# DatacakeWing.net
KiCad netlist of a schematic drawn in EAGLE
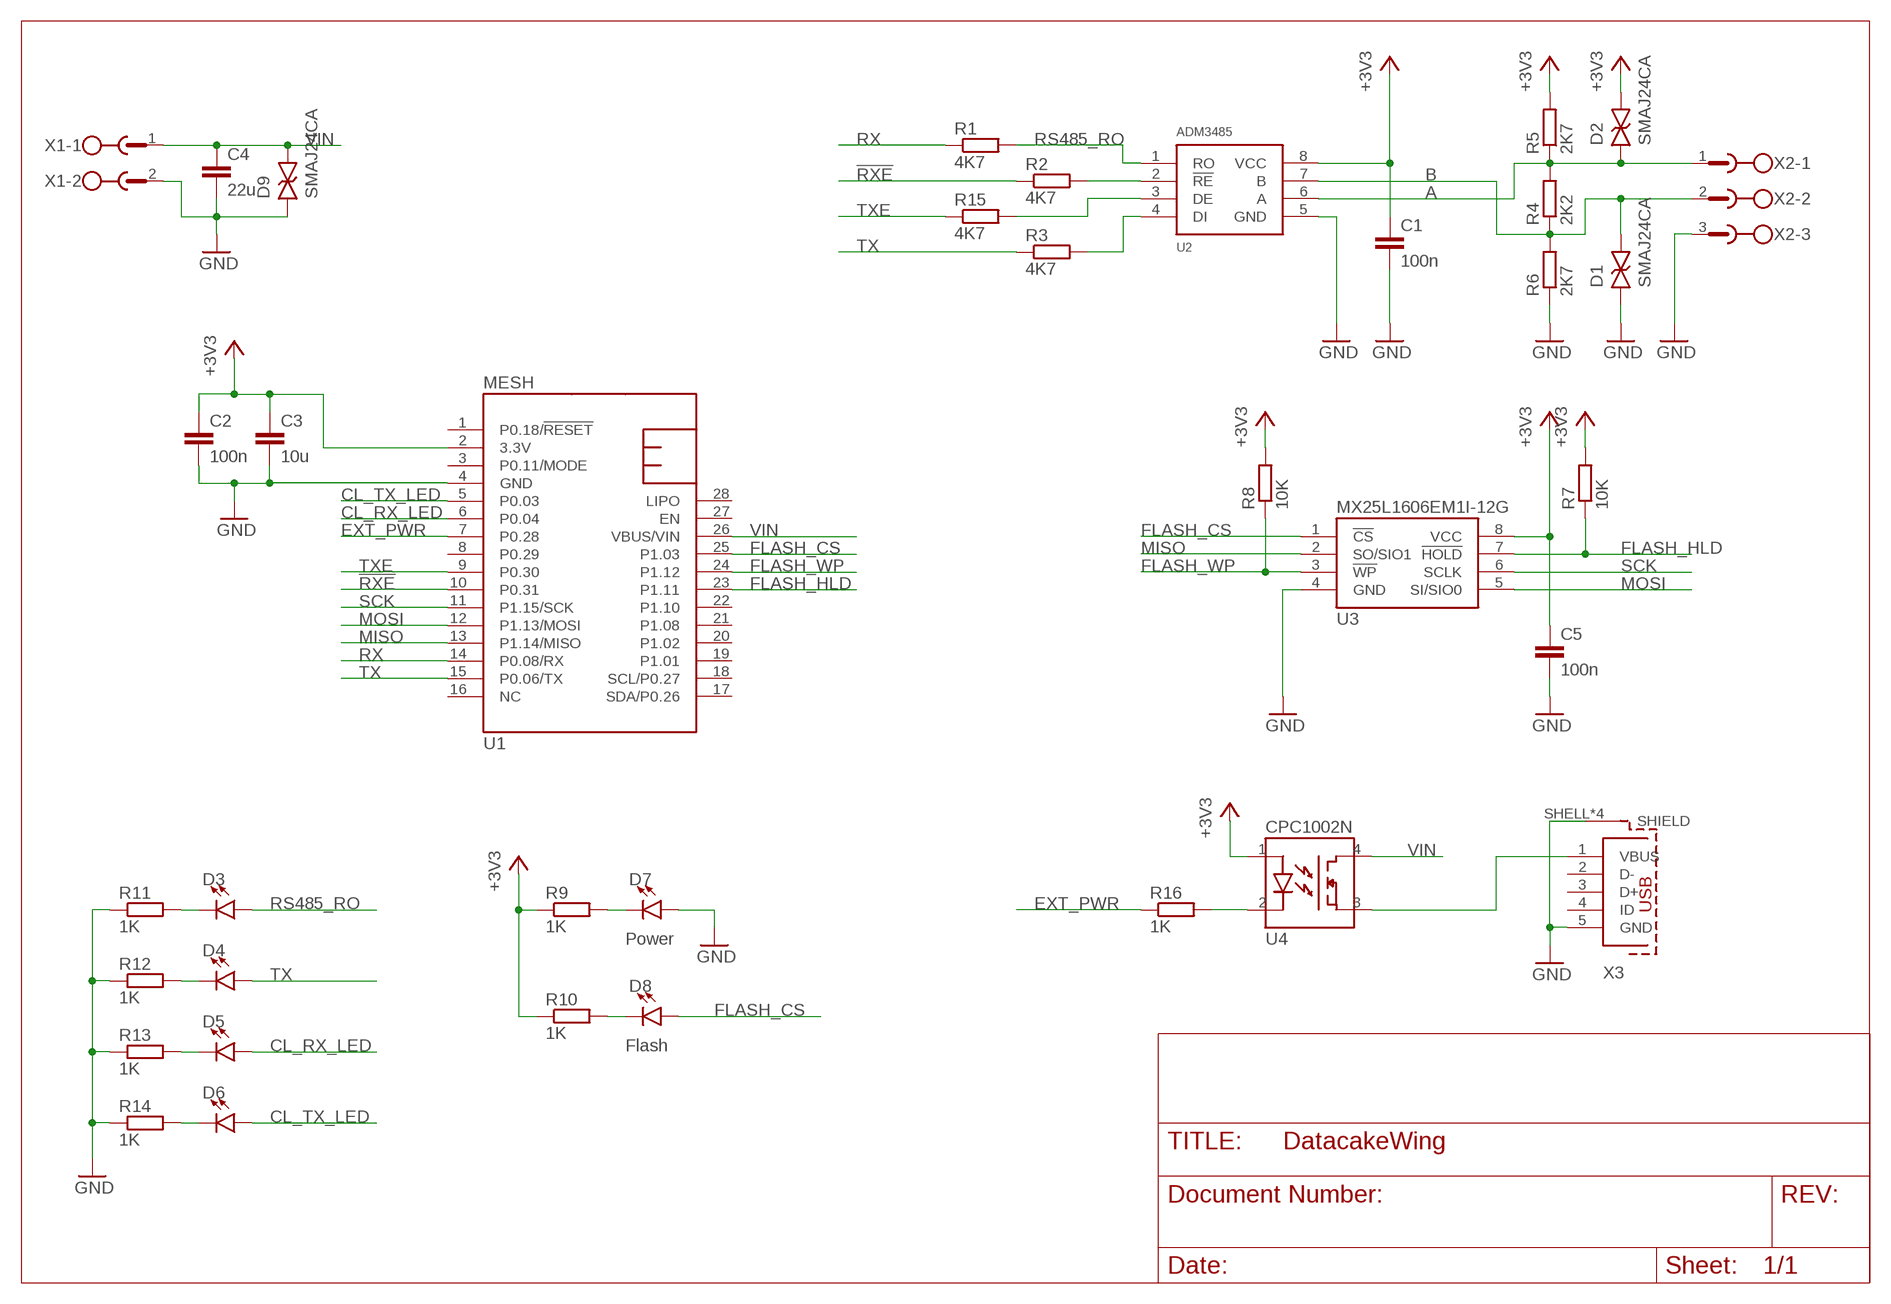
[diagram p0: schematic, sheet 1]

(export (version "E")
  (design (tool "Eeschema 10.0.6"))
  (components
    (comp (ref "C1")
      (value "100n")
      (footprint "eagle-import:C0603")
      (libsource (lib "eagle-import") (part "C-EUC0603"))
    )
    (comp (ref "C2")
      (value "100n")
      (footprint "eagle-import:C0603")
      (libsource (lib "eagle-import") (part "C-EUC0603"))
    )
    (comp (ref "C3")
      (value "10u")
      (footprint "eagle-import:C0603")
      (libsource (lib "eagle-import") (part "C-EUC0603"))
    )
    (comp (ref "C4")
      (value "22u")
      (footprint "eagle-import:C1210")
      (libsource (lib "eagle-import") (part "C-EUC1210"))
    )
    (comp (ref "C5")
      (value "100n")
      (footprint "eagle-import:C0603")
      (libsource (lib "eagle-import") (part "C-EUC0603"))
    )
    (comp (ref "D1")
      (value "SMAJ24CA")
      (footprint "eagle-import:DO-214AC")
      (libsource (lib "eagle-import") (part "SMAJ24CA"))
    )
    (comp (ref "D2")
      (value "SMAJ24CA")
      (footprint "eagle-import:DO-214AC")
      (libsource (lib "eagle-import") (part "SMAJ24CA"))
    )
    (comp (ref "D3")
      (value "LED0603")
      (footprint "eagle-import:LED-0603")
      (libsource (lib "eagle-import") (part "LED0603"))
    )
    (comp (ref "D4")
      (value "LED0603")
      (footprint "eagle-import:LED-0603")
      (libsource (lib "eagle-import") (part "LED0603"))
    )
    (comp (ref "D5")
      (value "LED0603")
      (footprint "eagle-import:LED-0603")
      (libsource (lib "eagle-import") (part "LED0603"))
    )
    (comp (ref "D6")
      (value "LED0603")
      (footprint "eagle-import:LED-0603")
      (libsource (lib "eagle-import") (part "LED0603"))
    )
    (comp (ref "D7")
      (value "LED0603")
      (footprint "eagle-import:LED-0603")
      (libsource (lib "eagle-import") (part "LED0603"))
    )
    (comp (ref "D8")
      (value "LED0603")
      (footprint "eagle-import:LED-0603")
      (libsource (lib "eagle-import") (part "LED0603"))
    )
    (comp (ref "D9")
      (value "SMAJ24CA")
      (footprint "eagle-import:DO-214AC")
      (libsource (lib "eagle-import") (part "SMAJ24CA"))
    )
    (comp (ref "R1")
      (value "4K7")
      (footprint "eagle-import:R0402")
      (libsource (lib "eagle-import") (part "R-EU_R0402"))
    )
    (comp (ref "R2")
      (value "4K7")
      (footprint "eagle-import:R0402")
      (libsource (lib "eagle-import") (part "R-EU_R0402"))
    )
    (comp (ref "R3")
      (value "4K7")
      (footprint "eagle-import:R0402")
      (libsource (lib "eagle-import") (part "R-EU_R0402"))
    )
    (comp (ref "R4")
      (value "2K2")
      (footprint "eagle-import:R0402")
      (libsource (lib "eagle-import") (part "R-EU_R0402"))
    )
    (comp (ref "R5")
      (value "2K7")
      (footprint "eagle-import:R0402")
      (libsource (lib "eagle-import") (part "R-EU_R0402"))
    )
    (comp (ref "R6")
      (value "2K7")
      (footprint "eagle-import:R0402")
      (libsource (lib "eagle-import") (part "R-EU_R0402"))
    )
    (comp (ref "R7")
      (value "10K")
      (footprint "eagle-import:R0402")
      (libsource (lib "eagle-import") (part "R-EU_R0402"))
    )
    (comp (ref "R8")
      (value "10K")
      (footprint "eagle-import:R0402")
      (libsource (lib "eagle-import") (part "R-EU_R0402"))
    )
    (comp (ref "R9")
      (value "1K")
      (footprint "eagle-import:R0402")
      (libsource (lib "eagle-import") (part "R-EU_R0402"))
    )
    (comp (ref "R10")
      (value "1K")
      (footprint "eagle-import:R0402")
      (libsource (lib "eagle-import") (part "R-EU_R0402"))
    )
    (comp (ref "R11")
      (value "1K")
      (footprint "eagle-import:R0402")
      (libsource (lib "eagle-import") (part "R-EU_R0402"))
    )
    (comp (ref "R12")
      (value "1K")
      (footprint "eagle-import:R0402")
      (libsource (lib "eagle-import") (part "R-EU_R0402"))
    )
    (comp (ref "R13")
      (value "1K")
      (footprint "eagle-import:R0402")
      (libsource (lib "eagle-import") (part "R-EU_R0402"))
    )
    (comp (ref "R14")
      (value "1K")
      (footprint "eagle-import:R0402")
      (libsource (lib "eagle-import") (part "R-EU_R0402"))
    )
    (comp (ref "R15")
      (value "4K7")
      (footprint "eagle-import:R0402")
      (libsource (lib "eagle-import") (part "R-EU_R0402"))
    )
    (comp (ref "R16")
      (value "1K")
      (footprint "eagle-import:R0402")
      (libsource (lib "eagle-import") (part "R-EU_R0402"))
    )
    (comp (ref "U1")
      (value "MESH")
      (footprint "eagle-import:FEATHERWING")
      (libsource (lib "eagle-import") (part "MESH"))
    )
    (comp (ref "U2")
      (value "ADM3485")
      (footprint "eagle-import:SO08-0.15")
      (libsource (lib "eagle-import") (part "ADM3485"))
    )
    (comp (ref "U3")
      (value "MX25L1606EM1I-12G")
      (footprint "eagle-import:SO08-0.15")
      (libsource (lib "eagle-import") (part "MX25L1606EM1I-12G"))
    )
    (comp (ref "U4")
      (value "CPC1002N")
      (footprint "eagle-import:CPC1002N")
      (libsource (lib "eagle-import") (part "CPC1002N"))
    )
    (comp (ref "X1")
      (value "MC1,5/2-G-3,5")
      (footprint "eagle-import:MC-2")
      (libsource (lib "eagle-import") (part "MC1,5/2-G-3,5"))
    )
    (comp (ref "X2")
      (value "MC1,5/3-G-3,5")
      (footprint "eagle-import:MC-3")
      (libsource (lib "eagle-import") (part "MC1,5/3-G-3,5"))
    )
    (comp (ref "X3")
      (value "629105136821")
      (footprint "eagle-import:629105136821")
      (libsource (lib "eagle-import") (part "629105136821"))
    )
  )
  (nets
    (net (code "1") (name "+3V3") (class "Default")
      (node (ref "C1") (pin "1") (pinfunction "1_1") (pintype "passive"))
      (node (ref "C2") (pin "1") (pinfunction "1_1") (pintype "passive"))
      (node (ref "C3") (pin "1") (pinfunction "1_1") (pintype "passive"))
      (node (ref "C5") (pin "1") (pinfunction "1_1") (pintype "passive"))
      (node (ref "D2") (pin "2") (pinfunction "P$2_2") (pintype "passive"))
      (node (ref "R10") (pin "1") (pinfunction "1_1") (pintype "passive"))
      (node (ref "R5") (pin "2") (pinfunction "2_2") (pintype "passive"))
      (node (ref "R7") (pin "2") (pinfunction "2_2") (pintype "passive"))
      (node (ref "R8") (pin "2") (pinfunction "2_2") (pintype "passive"))
      (node (ref "R9") (pin "1") (pinfunction "1_1") (pintype "passive"))
      (node (ref "U1") (pin "2") (pinfunction "3.3V_2") (pintype "power_in"))
      (node (ref "U2") (pin "8") (pinfunction "VCC_8") (pintype "bidirectional"))
      (node (ref "U3") (pin "8") (pinfunction "VCC_8") (pintype "bidirectional"))
      (node (ref "U4") (pin "1") (pinfunction "1_1") (pintype "passive"))
    )
    (net (code "2") (name "/A") (class "Default")
      (node (ref "D2") (pin "1") (pinfunction "P$1_1") (pintype "passive"))
      (node (ref "R4") (pin "2") (pinfunction "2_2") (pintype "passive"))
      (node (ref "R5") (pin "1") (pinfunction "1_1") (pintype "passive"))
      (node (ref "U2") (pin "6") (pinfunction "A_6") (pintype "bidirectional"))
      (node (ref "X2") (pin "1") (pinfunction "1_1") (pintype "passive"))
    )
    (net (code "3") (name "/B") (class "Default")
      (node (ref "D1") (pin "2") (pinfunction "P$2_2") (pintype "passive"))
      (node (ref "R4") (pin "1") (pinfunction "1_1") (pintype "passive"))
      (node (ref "R6") (pin "2") (pinfunction "2_2") (pintype "passive"))
      (node (ref "U2") (pin "7") (pinfunction "B_7") (pintype "bidirectional"))
      (node (ref "X2") (pin "2") (pinfunction "1_2") (pintype "passive"))
    )
    (net (code "4") (name "/CL_RX_LED") (class "Default")
      (node (ref "D5") (pin "A") (pinfunction "A_A") (pintype "passive"))
      (node (ref "U1") (pin "6") (pinfunction "P0.04_6") (pintype "bidirectional"))
    )
    (net (code "5") (name "/CL_TX_LED") (class "Default")
      (node (ref "D6") (pin "A") (pinfunction "A_A") (pintype "passive"))
      (node (ref "U1") (pin "5") (pinfunction "P0.03_5") (pintype "bidirectional"))
    )
    (net (code "6") (name "/EXT_PWR") (class "Default")
      (node (ref "R16") (pin "1") (pinfunction "1_1") (pintype "passive"))
      (node (ref "U1") (pin "7") (pinfunction "P0.28_7") (pintype "bidirectional"))
    )
    (net (code "7") (name "/FLASH_CS") (class "Default")
      (node (ref "D8") (pin "A") (pinfunction "A_A") (pintype "passive"))
      (node (ref "U1") (pin "25") (pinfunction "P1.03_25") (pintype "bidirectional"))
      (node (ref "U3") (pin "1") (pinfunction "~{CS}_1") (pintype "bidirectional"))
    )
    (net (code "8") (name "/FLASH_HLD") (class "Default")
      (node (ref "R7") (pin "1") (pinfunction "1_1") (pintype "passive"))
      (node (ref "U1") (pin "23") (pinfunction "P1.11_23") (pintype "bidirectional"))
      (node (ref "U3") (pin "7") (pinfunction "~{HOLD}_7") (pintype "bidirectional"))
    )
    (net (code "9") (name "/FLASH_WP") (class "Default")
      (node (ref "R8") (pin "1") (pinfunction "1_1") (pintype "passive"))
      (node (ref "U1") (pin "24") (pinfunction "P1.12_24") (pintype "bidirectional"))
      (node (ref "U3") (pin "3") (pinfunction "~{WP}_3") (pintype "bidirectional"))
    )
    (net (code "10") (name "/LIPO") (class "Default")
      (node (ref "U1") (pin "28") (pinfunction "LIPO_28") (pintype "power_in"))
    )
    (net (code "11") (name "/MISO") (class "Default")
      (node (ref "U1") (pin "13") (pinfunction "P1.14/MISO_13") (pintype "bidirectional"))
      (node (ref "U3") (pin "2") (pinfunction "SO/SIO1_2") (pintype "bidirectional"))
    )
    (net (code "12") (name "/MOSI") (class "Default")
      (node (ref "U1") (pin "12") (pinfunction "P1.13/MOSI_12") (pintype "bidirectional"))
      (node (ref "U3") (pin "5") (pinfunction "SI/SIO0_5") (pintype "bidirectional"))
    )
    (net (code "13") (name "/RS485_RO") (class "Default")
      (node (ref "D3") (pin "A") (pinfunction "A_A") (pintype "passive"))
      (node (ref "R1") (pin "2") (pinfunction "2_2") (pintype "passive"))
      (node (ref "U2") (pin "1") (pinfunction "RO_1") (pintype "bidirectional"))
    )
    (net (code "14") (name "/RX") (class "Default")
      (node (ref "R1") (pin "1") (pinfunction "1_1") (pintype "passive"))
      (node (ref "U1") (pin "14") (pinfunction "P0.08/RX_14") (pintype "bidirectional"))
    )
    (net (code "15") (name "/SCK") (class "Default")
      (node (ref "U1") (pin "11") (pinfunction "P1.15/SCK_11") (pintype "bidirectional"))
      (node (ref "U3") (pin "6") (pinfunction "SCLK_6") (pintype "bidirectional"))
    )
    (net (code "16") (name "/TX") (class "Default")
      (node (ref "D4") (pin "A") (pinfunction "A_A") (pintype "passive"))
      (node (ref "R3") (pin "1") (pinfunction "1_1") (pintype "passive"))
      (node (ref "U1") (pin "15") (pinfunction "P0.06/TX_15") (pintype "bidirectional"))
    )
    (net (code "17") (name "/TXE") (class "Default")
      (node (ref "R15") (pin "1") (pinfunction "1_1") (pintype "passive"))
      (node (ref "U1") (pin "9") (pinfunction "P0.30_9") (pintype "bidirectional"))
    )
    (net (code "18") (name "/VIN") (class "Default")
      (node (ref "C4") (pin "1") (pinfunction "1_1") (pintype "passive"))
      (node (ref "D9") (pin "2") (pinfunction "P$2_2") (pintype "passive"))
      (node (ref "U1") (pin "26") (pinfunction "VBUS/VIN_26") (pintype "power_in"))
      (node (ref "U4") (pin "4") (pinfunction "4_4") (pintype "passive"))
      (node (ref "X1") (pin "1") (pinfunction "1_1") (pintype "passive"))
    )
    (net (code "19") (name "/~{RXE}") (class "Default")
      (node (ref "R2") (pin "1") (pinfunction "1_1") (pintype "passive"))
      (node (ref "U1") (pin "10") (pinfunction "P0.31_10") (pintype "bidirectional"))
    )
    (net (code "20") (name "GND") (class "Default")
      (node (ref "C1") (pin "2") (pinfunction "2_2") (pintype "passive"))
      (node (ref "C2") (pin "2") (pinfunction "2_2") (pintype "passive"))
      (node (ref "C3") (pin "2") (pinfunction "2_2") (pintype "passive"))
      (node (ref "C4") (pin "2") (pinfunction "2_2") (pintype "passive"))
      (node (ref "C5") (pin "2") (pinfunction "2_2") (pintype "passive"))
      (node (ref "D1") (pin "1") (pinfunction "P$1_1") (pintype "passive"))
      (node (ref "D7") (pin "A") (pinfunction "A_A") (pintype "passive"))
      (node (ref "D9") (pin "1") (pinfunction "P$1_1") (pintype "passive"))
      (node (ref "R11") (pin "1") (pinfunction "1_1") (pintype "passive"))
      (node (ref "R12") (pin "1") (pinfunction "1_1") (pintype "passive"))
      (node (ref "R13") (pin "1") (pinfunction "1_1") (pintype "passive"))
      (node (ref "R14") (pin "1") (pinfunction "1_1") (pintype "passive"))
      (node (ref "R6") (pin "1") (pinfunction "1_1") (pintype "passive"))
      (node (ref "U1") (pin "4") (pinfunction "GND_4") (pintype "power_in"))
      (node (ref "U2") (pin "5") (pinfunction "GND_5") (pintype "bidirectional"))
      (node (ref "U3") (pin "4") (pinfunction "GND_4") (pintype "bidirectional"))
      (node (ref "X1") (pin "2") (pinfunction "1_2") (pintype "passive"))
      (node (ref "X2") (pin "3") (pinfunction "1_3") (pintype "passive"))
      (node (ref "X3") (pin "5") (pinfunction "GND_5") (pintype "passive"))
      (node (ref "X3") (pin "SHELL") (pinfunction "SHIELD_SHELL") (pintype "passive"))
      (node (ref "X3") (pin "SHELL1") (pinfunction "SHIELD_SHELL1") (pintype "passive"))
      (node (ref "X3") (pin "SHELL2") (pinfunction "SHIELD_SHELL2") (pintype "passive"))
      (node (ref "X3") (pin "SHELL3") (pinfunction "SHIELD_SHELL3") (pintype "passive"))
    )
    (net (code "21") (name "Net-(D3-PadC)") (class "Default")
      (node (ref "D3") (pin "C") (pinfunction "C_C") (pintype "passive"))
      (node (ref "R11") (pin "2") (pinfunction "2_2") (pintype "passive"))
    )
    (net (code "22") (name "Net-(D4-PadC)") (class "Default")
      (node (ref "D4") (pin "C") (pinfunction "C_C") (pintype "passive"))
      (node (ref "R12") (pin "2") (pinfunction "2_2") (pintype "passive"))
    )
    (net (code "23") (name "Net-(D5-PadC)") (class "Default")
      (node (ref "D5") (pin "C") (pinfunction "C_C") (pintype "passive"))
      (node (ref "R13") (pin "2") (pinfunction "2_2") (pintype "passive"))
    )
    (net (code "24") (name "Net-(D6-PadC)") (class "Default")
      (node (ref "D6") (pin "C") (pinfunction "C_C") (pintype "passive"))
      (node (ref "R14") (pin "2") (pinfunction "2_2") (pintype "passive"))
    )
    (net (code "25") (name "Net-(D7-PadC)") (class "Default")
      (node (ref "D7") (pin "C") (pinfunction "C_C") (pintype "passive"))
      (node (ref "R9") (pin "2") (pinfunction "2_2") (pintype "passive"))
    )
    (net (code "26") (name "Net-(D8-PadC)") (class "Default")
      (node (ref "D8") (pin "C") (pinfunction "C_C") (pintype "passive"))
      (node (ref "R10") (pin "2") (pinfunction "2_2") (pintype "passive"))
    )
    (net (code "27") (name "Net-(R16-Pad2)") (class "Default")
      (node (ref "R16") (pin "2") (pinfunction "2_2") (pintype "passive"))
      (node (ref "U4") (pin "2") (pinfunction "2_2") (pintype "passive"))
    )
    (net (code "28") (name "Net-(U2-DE)") (class "Default")
      (node (ref "R15") (pin "2") (pinfunction "2_2") (pintype "passive"))
      (node (ref "U2") (pin "3") (pinfunction "DE_3") (pintype "bidirectional"))
    )
    (net (code "29") (name "Net-(U2-DI)") (class "Default")
      (node (ref "R3") (pin "2") (pinfunction "2_2") (pintype "passive"))
      (node (ref "U2") (pin "4") (pinfunction "DI_4") (pintype "bidirectional"))
    )
    (net (code "30") (name "Net-(U2-~{RE})") (class "Default")
      (node (ref "R2") (pin "2") (pinfunction "2_2") (pintype "passive"))
      (node (ref "U2") (pin "2") (pinfunction "~{RE}_2") (pintype "bidirectional"))
    )
    (net (code "31") (name "Net-(X3-VBUS)") (class "Default")
      (node (ref "U4") (pin "3") (pinfunction "3_3") (pintype "passive"))
      (node (ref "X3") (pin "1") (pinfunction "VBUS_1") (pintype "passive"))
    )
    (net (code "32") (name "unconnected-(U1-EN-Pad27)") (class "Default")
      (node (ref "U1") (pin "27") (pinfunction "EN_27") (pintype "passive"))
    )
    (net (code "33") (name "unconnected-(U1-NC-Pad16)") (class "Default")
      (node (ref "U1") (pin "16") (pinfunction "NC_16") (pintype "passive"))
    )
    (net (code "34") (name "unconnected-(U1-P0.11{slash}MODE-Pad3)") (class "Default")
      (node (ref "U1") (pin "3") (pinfunction "P0.11/MODE_3") (pintype "passive"))
    )
    (net (code "35") (name "unconnected-(U1-P0.18{slash}~{RESET}-Pad1)") (class "Default")
      (node (ref "U1") (pin "1") (pinfunction "P0.18/~{RESET}_1") (pintype "input"))
    )
    (net (code "36") (name "unconnected-(U1-P0.29-Pad8)") (class "Default")
      (node (ref "U1") (pin "8") (pinfunction "P0.29_8") (pintype "bidirectional"))
    )
    (net (code "37") (name "unconnected-(U1-P1.01-Pad19)") (class "Default")
      (node (ref "U1") (pin "19") (pinfunction "P1.01_19") (pintype "bidirectional"))
    )
    (net (code "38") (name "unconnected-(U1-P1.02-Pad20)") (class "Default")
      (node (ref "U1") (pin "20") (pinfunction "P1.02_20") (pintype "bidirectional"))
    )
    (net (code "39") (name "unconnected-(U1-P1.08-Pad21)") (class "Default")
      (node (ref "U1") (pin "21") (pinfunction "P1.08_21") (pintype "bidirectional"))
    )
    (net (code "40") (name "unconnected-(U1-P1.10-Pad22)") (class "Default")
      (node (ref "U1") (pin "22") (pinfunction "P1.10_22") (pintype "bidirectional"))
    )
    (net (code "41") (name "unconnected-(U1-SCL{slash}P0.27-Pad18)") (class "Default")
      (node (ref "U1") (pin "18") (pinfunction "SCL/P0.27_18") (pintype "bidirectional"))
    )
    (net (code "42") (name "unconnected-(U1-SDA{slash}P0.26-Pad17)") (class "Default")
      (node (ref "U1") (pin "17") (pinfunction "SDA/P0.26_17") (pintype "bidirectional"))
    )
    (net (code "43") (name "unconnected-(X3-D+-Pad3)") (class "Default")
      (node (ref "X3") (pin "3") (pinfunction "D+_3") (pintype "passive"))
    )
    (net (code "44") (name "unconnected-(X3-D--Pad2)") (class "Default")
      (node (ref "X3") (pin "2") (pinfunction "D-_2") (pintype "passive"))
    )
    (net (code "45") (name "unconnected-(X3-ID-Pad4)") (class "Default")
      (node (ref "X3") (pin "4") (pinfunction "ID_4") (pintype "passive"))
    )
  )
)
